# STM32G4.net
KiCad netlist of a schematic drawn in Altium Designer
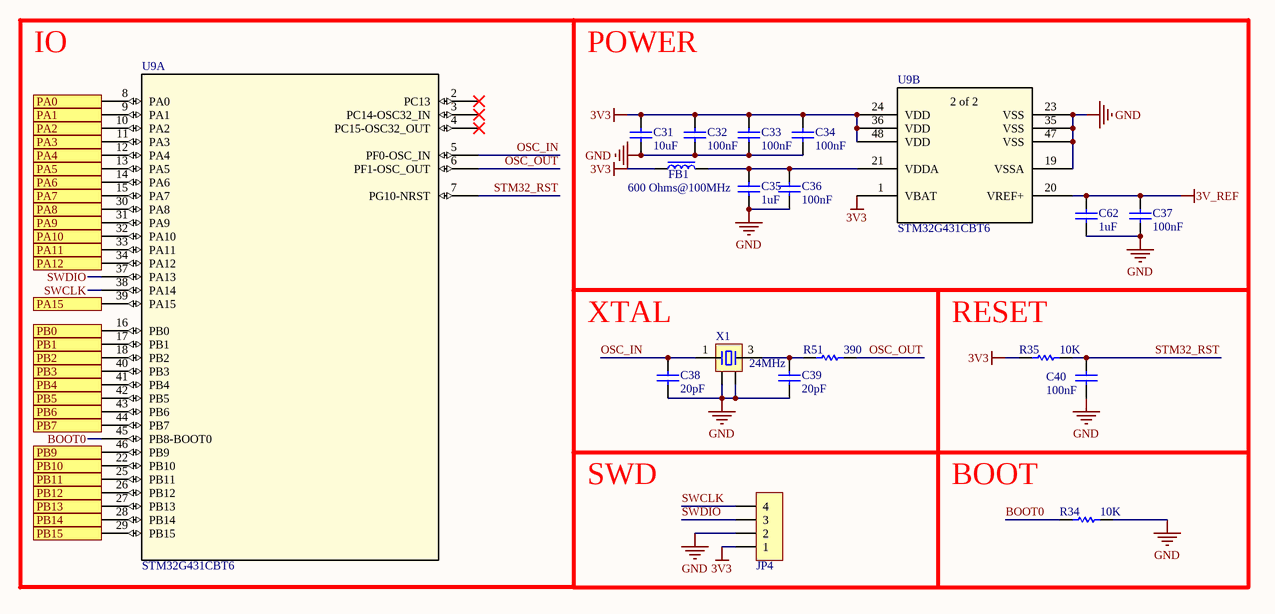
[diagram p0: STM32G4.SchDoc]

(export (version "E")
  (design (tool "Eeschema 10.0.6"))
  (components
    (comp (ref "C31") (value "10uF") (footprint "C0805") (libsource (lib "Cap") (part "Cap")))
    (comp (ref "C32") (value "100nF") (footprint "C0402") (libsource (lib "Cap") (part "Cap")))
    (comp (ref "C33") (value "100nF") (footprint "C0402") (libsource (lib "Cap") (part "Cap")))
    (comp (ref "C34") (value "100nF") (footprint "C0402") (libsource (lib "Cap") (part "Cap")))
    (comp (ref "C35") (value "1uF") (footprint "C0603") (libsource (lib "Cap") (part "Cap")))
    (comp (ref "C36") (value "100nF") (footprint "C0402") (libsource (lib "Cap") (part "Cap")))
    (comp (ref "C37") (value "100nF") (footprint "C0402") (libsource (lib "Cap") (part "Cap")))
    (comp (ref "C38") (value "20pF") (footprint "C0402") (libsource (lib "Cap") (part "Cap")))
    (comp (ref "C39") (value "20pF") (footprint "C0402") (libsource (lib "Cap") (part "Cap")))
    (comp (ref "C40") (value "100nF") (footprint "C0402") (libsource (lib "Cap") (part "Cap")))
    (comp (ref "C62") (value "1uF") (footprint "C0603") (libsource (lib "Cap") (part "Cap")))
    (comp (ref "FB1")
      (value "600 Ohms@100MHz")
      (footprint "FB 0402")
      (description "磁珠")
      (libsource (lib "All lib") (part "FB"))
    )
    (comp (ref "JP4")
      (value "HDR-1X4")
      (footprint "XH2.54-4P_H")
      (description "4P接插件")
      (fields (field (name "版权归属") "源创客"))
      (libsource (lib "All lib") (part "Header 4P"))
    )
    (comp (ref "R34") (value "10K") (footprint "R0402") (libsource (lib "Res") (part "RES")))
    (comp (ref "R35") (value "10K") (footprint "R0402") (libsource (lib "Res") (part "RES")))
    (comp (ref "R51") (value "390") (footprint "R0402") (libsource (lib "Res") (part "RES")))
    (comp (ref "U9")
      (value "STM32G431CBT6")
      (footprint "LQFP48 7X7_L")
      (description "No Description Available")
      (fields (field (name "COPYRIGHT") "Copyright (C) 2022 Ultra Librarian. All rights reserved."))
      (libsource (lib "All lib") (part "STM32G431CBT6"))
    )
    (comp (ref "X1")
      (value "24MHz")
      (footprint "XTAL-3225")
      (description "4脚晶振")
      (fields (field (name "版权归属") "源创客"))
      (libsource (lib "All lib") (part "XTAL-4"))
    )
  )
  (nets
    (net (code "1") (name "/BOOT0") (class "Default")
      (node (ref "R34") (pin "1") (pinfunction "1_1") (pintype "passive"))
      (node (ref "U9") (pin "45") (pinfunction "PB8-BOOT0_45") (pintype "bidirectional"))
    )
    (net (code "2") (name "/OSC_IN") (class "Default")
      (node (ref "C38") (pin "2") (pinfunction "2_2") (pintype "passive"))
      (node (ref "U9") (pin "5") (pinfunction "PF0-OSC_IN_5") (pintype "bidirectional"))
      (node (ref "X1") (pin "1") (pinfunction "1_1") (pintype "passive"))
    )
    (net (code "3") (name "/OSC_OUT") (class "Default")
      (node (ref "R51") (pin "2") (pinfunction "2_2") (pintype "passive"))
      (node (ref "U9") (pin "6") (pinfunction "PF1-OSC_OUT_6") (pintype "bidirectional"))
    )
    (net (code "4") (name "/PA0") (class "Default")
      (node (ref "U9") (pin "8") (pinfunction "PA0_8") (pintype "bidirectional"))
    )
    (net (code "5") (name "/PA1") (class "Default")
      (node (ref "U9") (pin "9") (pinfunction "PA1_9") (pintype "bidirectional"))
    )
    (net (code "6") (name "/PA2") (class "Default")
      (node (ref "U9") (pin "10") (pinfunction "PA2_10") (pintype "bidirectional"))
    )
    (net (code "7") (name "/PA3") (class "Default")
      (node (ref "U9") (pin "11") (pinfunction "PA3_11") (pintype "bidirectional"))
    )
    (net (code "8") (name "/PA4") (class "Default")
      (node (ref "U9") (pin "12") (pinfunction "PA4_12") (pintype "bidirectional"))
    )
    (net (code "9") (name "/PA5") (class "Default")
      (node (ref "U9") (pin "13") (pinfunction "PA5_13") (pintype "bidirectional"))
    )
    (net (code "10") (name "/PA6") (class "Default")
      (node (ref "U9") (pin "14") (pinfunction "PA6_14") (pintype "bidirectional"))
    )
    (net (code "11") (name "/PA7") (class "Default")
      (node (ref "U9") (pin "15") (pinfunction "PA7_15") (pintype "bidirectional"))
    )
    (net (code "12") (name "/PA8") (class "Default")
      (node (ref "U9") (pin "30") (pinfunction "PA8_30") (pintype "bidirectional"))
    )
    (net (code "13") (name "/PA9") (class "Default")
      (node (ref "U9") (pin "31") (pinfunction "PA9_31") (pintype "bidirectional"))
    )
    (net (code "14") (name "/PA10") (class "Default")
      (node (ref "U9") (pin "32") (pinfunction "PA10_32") (pintype "bidirectional"))
    )
    (net (code "15") (name "/PA11") (class "Default")
      (node (ref "U9") (pin "33") (pinfunction "PA11_33") (pintype "bidirectional"))
    )
    (net (code "16") (name "/PA12") (class "Default")
      (node (ref "U9") (pin "34") (pinfunction "PA12_34") (pintype "bidirectional"))
    )
    (net (code "17") (name "/PA15") (class "Default")
      (node (ref "U9") (pin "39") (pinfunction "PA15_39") (pintype "bidirectional"))
    )
    (net (code "18") (name "/PB0") (class "Default")
      (node (ref "U9") (pin "16") (pinfunction "PB0_16") (pintype "bidirectional"))
    )
    (net (code "19") (name "/PB1") (class "Default")
      (node (ref "U9") (pin "17") (pinfunction "PB1_17") (pintype "bidirectional"))
    )
    (net (code "20") (name "/PB2") (class "Default")
      (node (ref "U9") (pin "18") (pinfunction "PB2_18") (pintype "bidirectional"))
    )
    (net (code "21") (name "/PB3") (class "Default")
      (node (ref "U9") (pin "40") (pinfunction "PB3_40") (pintype "bidirectional"))
    )
    (net (code "22") (name "/PB4") (class "Default")
      (node (ref "U9") (pin "41") (pinfunction "PB4_41") (pintype "bidirectional"))
    )
    (net (code "23") (name "/PB5") (class "Default")
      (node (ref "U9") (pin "42") (pinfunction "PB5_42") (pintype "bidirectional"))
    )
    (net (code "24") (name "/PB6") (class "Default")
      (node (ref "U9") (pin "43") (pinfunction "PB6_43") (pintype "bidirectional"))
    )
    (net (code "25") (name "/PB7") (class "Default")
      (node (ref "U9") (pin "44") (pinfunction "PB7_44") (pintype "bidirectional"))
    )
    (net (code "26") (name "/PB9") (class "Default")
      (node (ref "U9") (pin "46") (pinfunction "PB9_46") (pintype "bidirectional"))
    )
    (net (code "27") (name "/PB10") (class "Default")
      (node (ref "U9") (pin "22") (pinfunction "PB10_22") (pintype "bidirectional"))
    )
    (net (code "28") (name "/PB11") (class "Default")
      (node (ref "U9") (pin "25") (pinfunction "PB11_25") (pintype "bidirectional"))
    )
    (net (code "29") (name "/PB12") (class "Default")
      (node (ref "U9") (pin "26") (pinfunction "PB12_26") (pintype "bidirectional"))
    )
    (net (code "30") (name "/PB13") (class "Default")
      (node (ref "U9") (pin "27") (pinfunction "PB13_27") (pintype "bidirectional"))
    )
    (net (code "31") (name "/PB14") (class "Default")
      (node (ref "U9") (pin "28") (pinfunction "PB14_28") (pintype "bidirectional"))
    )
    (net (code "32") (name "/PB15") (class "Default")
      (node (ref "U9") (pin "29") (pinfunction "PB15_29") (pintype "bidirectional"))
    )
    (net (code "33") (name "/STM32_RST") (class "Default")
      (node (ref "C40") (pin "2") (pinfunction "2_2") (pintype "passive"))
      (node (ref "R35") (pin "2") (pinfunction "2_2") (pintype "passive"))
      (node (ref "U9") (pin "7") (pinfunction "PG10-NRST_7") (pintype "bidirectional"))
    )
    (net (code "34") (name "/SWCLK") (class "Default")
      (node (ref "JP4") (pin "4") (pinfunction "4_4") (pintype "passive"))
      (node (ref "U9") (pin "38") (pinfunction "PA14_38") (pintype "bidirectional"))
    )
    (net (code "35") (name "/SWDIO") (class "Default")
      (node (ref "JP4") (pin "3") (pinfunction "3_3") (pintype "passive"))
      (node (ref "U9") (pin "37") (pinfunction "PA13_37") (pintype "bidirectional"))
    )
    (net (code "36") (name "3V3") (class "Default")
      (node (ref "C31") (pin "2") (pinfunction "2_2") (pintype "passive"))
      (node (ref "C32") (pin "2") (pinfunction "2_2") (pintype "passive"))
      (node (ref "C33") (pin "2") (pinfunction "2_2") (pintype "passive"))
      (node (ref "C34") (pin "2") (pinfunction "2_2") (pintype "passive"))
      (node (ref "FB1") (pin "1") (pinfunction "1_1") (pintype "passive"))
      (node (ref "JP4") (pin "1") (pinfunction "1_1") (pintype "passive"))
      (node (ref "R35") (pin "1") (pinfunction "1_1") (pintype "passive"))
      (node (ref "U9") (pin "1") (pinfunction "VBAT_1") (pintype "power_in"))
      (node (ref "U9") (pin "24") (pinfunction "VDD_24") (pintype "power_in"))
      (node (ref "U9") (pin "36") (pinfunction "VDD_36") (pintype "power_in"))
      (node (ref "U9") (pin "48") (pinfunction "VDD_48") (pintype "power_in"))
    )
    (net (code "37") (name "3V_REF") (class "Default")
      (node (ref "C37") (pin "1") (pinfunction "1_1") (pintype "passive"))
      (node (ref "C62") (pin "1") (pinfunction "1_1") (pintype "passive"))
      (node (ref "U9") (pin "20") (pinfunction "VREF+_20") (pintype "power_in"))
    )
    (net (code "38") (name "GND") (class "Default")
      (node (ref "C31") (pin "1") (pinfunction "1_1") (pintype "passive"))
      (node (ref "C32") (pin "1") (pinfunction "1_1") (pintype "passive"))
      (node (ref "C33") (pin "1") (pinfunction "1_1") (pintype "passive"))
      (node (ref "C34") (pin "1") (pinfunction "1_1") (pintype "passive"))
      (node (ref "C35") (pin "2") (pinfunction "2_2") (pintype "passive"))
      (node (ref "C36") (pin "2") (pinfunction "2_2") (pintype "passive"))
      (node (ref "C37") (pin "2") (pinfunction "2_2") (pintype "passive"))
      (node (ref "C38") (pin "1") (pinfunction "1_1") (pintype "passive"))
      (node (ref "C39") (pin "1") (pinfunction "1_1") (pintype "passive"))
      (node (ref "C40") (pin "1") (pinfunction "1_1") (pintype "passive"))
      (node (ref "C62") (pin "2") (pinfunction "2_2") (pintype "passive"))
      (node (ref "JP4") (pin "2") (pinfunction "2_2") (pintype "passive"))
      (node (ref "R34") (pin "2") (pinfunction "2_2") (pintype "passive"))
      (node (ref "U9") (pin "19") (pinfunction "VSSA_19") (pintype "power_in"))
      (node (ref "U9") (pin "23") (pinfunction "VSS_23") (pintype "power_in"))
      (node (ref "U9") (pin "35") (pinfunction "VSS_35") (pintype "power_in"))
      (node (ref "U9") (pin "47") (pinfunction "VSS_47") (pintype "power_in"))
      (node (ref "X1") (pin "2") (pinfunction "2_2") (pintype "passive"))
      (node (ref "X1") (pin "4") (pinfunction "4_4") (pintype "passive"))
    )
    (net (code "39") (name "Net-(C39-Pad2)") (class "Default")
      (node (ref "C39") (pin "2") (pinfunction "2_2") (pintype "passive"))
      (node (ref "R51") (pin "1") (pinfunction "1_1") (pintype "passive"))
      (node (ref "X1") (pin "3") (pinfunction "3_3") (pintype "passive"))
    )
    (net (code "40") (name "Net-(U9B-VDDA)") (class "Default")
      (node (ref "C35") (pin "1") (pinfunction "1_1") (pintype "passive"))
      (node (ref "C36") (pin "1") (pinfunction "1_1") (pintype "passive"))
      (node (ref "FB1") (pin "2") (pinfunction "2_2") (pintype "passive"))
      (node (ref "U9") (pin "21") (pinfunction "VDDA_21") (pintype "power_in"))
    )
    (net (code "41") (name "unconnected-(U9A-PC13-Pad2)") (class "Default")
      (node (ref "U9") (pin "2") (pinfunction "PC13_2") (pintype "bidirectional+no_connect"))
    )
    (net (code "42") (name "unconnected-(U9A-PC14-OSC32_IN-Pad3)") (class "Default")
      (node (ref "U9") (pin "3") (pinfunction "PC14-OSC32_IN_3") (pintype "bidirectional+no_connect"))
    )
    (net (code "43") (name "unconnected-(U9A-PC15-OSC32_OUT-Pad4)") (class "Default")
      (node (ref "U9") (pin "4") (pinfunction "PC15-OSC32_OUT_4") (pintype "bidirectional+no_connect"))
    )
  )
)
